# Nixie_Embedded_Supply.net
KiCad netlist of a schematic drawn in Altium Designer
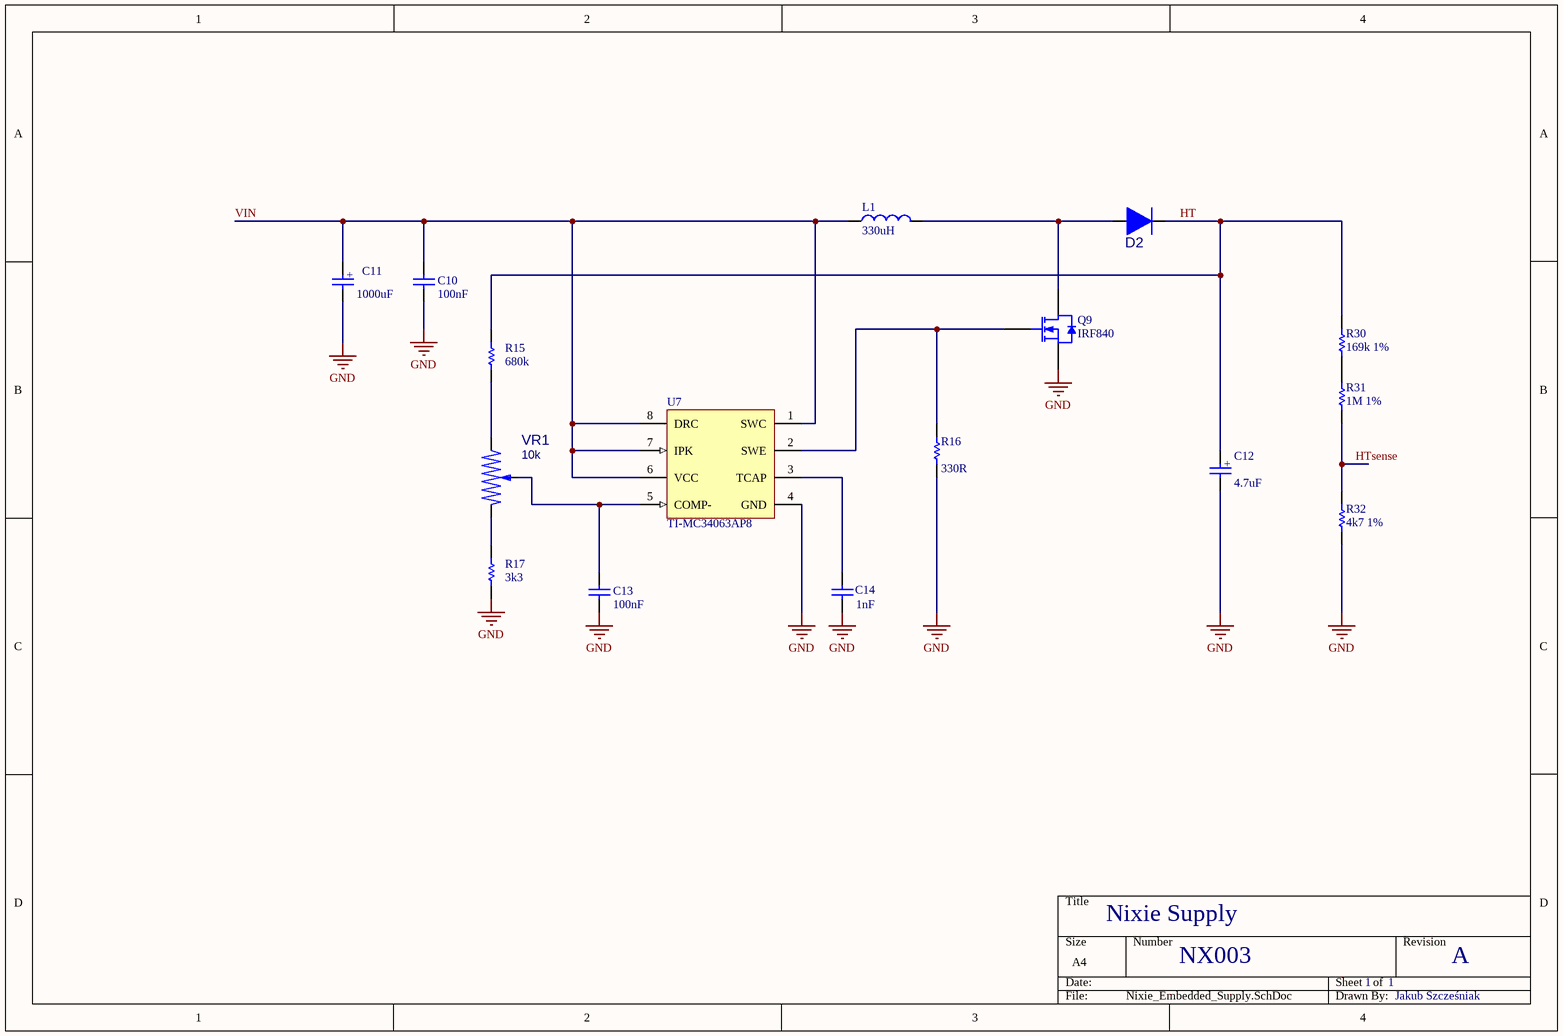
[diagram p0: Nixie_Embedded_Supply.SchDoc]

(export (version "E")
  (design (tool "Eeschema 10.0.6"))
  (components
    (comp (ref "C10")
      (value "100nF")
      (footprint "CAPC0805(2012)100_M")
      (description "CAP 100nF 16V ±5% 0805 (2012 Metric) Thickness 1mm SMD")
      (fields (field (name "TOLERANCE") "±5%") (field (name "Comment") "CAP 100nF 16V 0805(2012)"))
      (libsource (lib "Altium Content Vault") (part "CMP-1036-04400-1"))
    )
    (comp (ref "C11")
      (value "1000uF")
      (footprint "CAPsmd_rad10")
      (fields (field (name "Comment") "CAP_rad16x10"))
      (libsource (lib "Nixie_Supply") (part "CAP_rad16x10"))
    )
    (comp (ref "C12")
      (value "4.7uF")
      (footprint "CAP_HV")
      (fields (field (name "Comment") "CAP_HV"))
      (libsource (lib "Nixie_Supply") (part "CAP_HV"))
    )
    (comp (ref "C13")
      (value "100nF")
      (footprint "CAPC0805(2012)100_M")
      (description "CAP 100nF 16V ±5% 0805 (2012 Metric) Thickness 1mm SMD")
      (fields (field (name "TOLERANCE") "±5%") (field (name "Comment") "CAP 100nF 16V 0805(2012)"))
      (libsource (lib "Altium Content Vault") (part "CMP-1036-04400-1"))
    )
    (comp (ref "C14")
      (value "1nF")
      (footprint "CAPC0805(2012)100_M")
      (description "CAP 1nF 25V ±1% 0805 (2012 Metric) Thickness 1mm SMD")
      (fields (field (name "TOLERANCE") "±1%") (field (name "Comment") "CAP 1nF 25V 0805(2012)"))
      (libsource (lib "Altium Content Vault") (part "CMP-1036-02963-1"))
    )
    (comp (ref "D2")
      (value "BYV29-400")
      (footprint "D2PAK")
      (fields (field (name "PART NUMBER") "104-5508"))
      (libsource (lib "Nixie_Supply") (part "BYV29-400"))
    )
    (comp (ref "L1") (value "330uH") (footprint "Coil") (libsource (lib "Nixie_Supply") (part "L")))
    (comp (ref "Q9") (value "IRF840") (footprint "D2PAK") (libsource (lib "Nixie_Supply") (part "IRF840")))
    (comp (ref "R15")
      (value "680k")
      (footprint "RESC0805(2012)_M")
      (description "680K 0.125W 5% 0805 (2012 Metric)  SMD")
      (fields (field (name "POWER") "0.125 W") (field (name "TOLERANCE") "5 %"))
      (libsource (lib "Altium Content Vault") (part "CMP-1013-00142-1"))
    )
    (comp (ref "R16")
      (value "330R")
      (footprint "RESC0805(2012)_M")
      (description "330R 0.125W 5% 0805 (2012 Metric)  SMD")
      (fields (field (name "TOLERANCE") "5 %") (field (name "POWER") "0.125 W"))
      (libsource (lib "Altium Content Vault") (part "CMP-1013-00062-1"))
    )
    (comp (ref "R17")
      (value "3k3")
      (footprint "RESC0805(2012)_M")
      (description "3K3 0.125W 1% 0805 (2012 Metric)  SMD")
      (fields (field (name "TOLERANCE") "1 %") (field (name "POWER") "0.125 W"))
      (libsource (lib "Altium Content Vault") (part "CMP-1013-00567-1"))
    )
    (comp (ref "R30")
      (value "169k 1%")
      (footprint "RESC0805(2012)_M")
      (description "169K 0.125W 1% 0805 (2012 Metric)  SMD")
      (fields (field (name "POWER") "0.125 W") (field (name "TOLERANCE") "1 %"))
      (libsource (lib "Altium Content Vault") (part "CMP-1013-00760-1"))
    )
    (comp (ref "R31")
      (value "1M 1%")
      (footprint "RESC0805(2012)_M")
      (description "1M 0.125W 1% 0805 (2012 Metric)  SMD")
      (fields (field (name "POWER") "0.125 W") (field (name "TOLERANCE") "1 %"))
      (libsource (lib "Altium Content Vault") (part "CMP-1013-00849-1"))
    )
    (comp (ref "R32")
      (value "4k7 1%")
      (footprint "RESC0805(2012)_M")
      (description "4K7 0.125W 1% 0805 (2012 Metric)  SMD")
      (fields (field (name "POWER") "0.125 W") (field (name "TOLERANCE") "1 %"))
      (libsource (lib "Altium Content Vault") (part "RES"))
    )
    (comp (ref "U7")
      (value "TI-MC34063AP8")
      (footprint "SOIC8")
      (libsource (lib "Nixie_Supply") (part "TI-MC34063AP8"))
    )
    (comp (ref "VR1")
      (value "10k")
      (footprint "POT7x5")
      (description "Potentiometer")
      (fields (field (name "PART NUMBER") "119-1725"))
      (libsource (lib "Nixie_Supply") (part "RESPOT_ST-V01"))
    )
  )
  (nets
    (net (code "1") (name "/HT") (class "Default")
      (node (ref "C12") (pin "1") (pinfunction "1_1") (pintype "passive"))
      (node (ref "D2") (pin "2") (pinfunction "K_2") (pintype "passive"))
      (node (ref "R15") (pin "2") (pinfunction "2_2") (pintype "passive"))
      (node (ref "R30") (pin "2") (pinfunction "2_2") (pintype "passive"))
    )
    (net (code "2") (name "/HTsense") (class "Default")
      (node (ref "R31") (pin "1") (pinfunction "1_1") (pintype "passive"))
      (node (ref "R32") (pin "2") (pinfunction "2_2") (pintype "passive"))
    )
    (net (code "3") (name "/VIN") (class "Default")
      (node (ref "C10") (pin "2") (pinfunction "2_2") (pintype "passive"))
      (node (ref "C11") (pin "1") (pinfunction "1_1") (pintype "passive"))
      (node (ref "L1") (pin "1") (pinfunction "1_1") (pintype "passive"))
      (node (ref "U7") (pin "1") (pinfunction "SWC_1") (pintype "open_collector"))
      (node (ref "U7") (pin "6") (pinfunction "VCC_6") (pintype "power_in"))
      (node (ref "U7") (pin "7") (pinfunction "IPK_7") (pintype "input"))
      (node (ref "U7") (pin "8") (pinfunction "DRC_8") (pintype "open_collector"))
    )
    (net (code "4") (name "GND") (class "Default")
      (node (ref "C10") (pin "1") (pinfunction "1_1") (pintype "passive"))
      (node (ref "C11") (pin "2") (pinfunction "2_2") (pintype "passive"))
      (node (ref "C12") (pin "2") (pinfunction "2_2") (pintype "passive"))
      (node (ref "C13") (pin "1") (pinfunction "1_1") (pintype "passive"))
      (node (ref "C14") (pin "1") (pinfunction "1_1") (pintype "passive"))
      (node (ref "Q9") (pin "3") (pinfunction "S_3") (pintype "passive"))
      (node (ref "R16") (pin "1") (pinfunction "1_1") (pintype "passive"))
      (node (ref "R17") (pin "1") (pinfunction "1_1") (pintype "passive"))
      (node (ref "R32") (pin "1") (pinfunction "1_1") (pintype "passive"))
      (node (ref "U7") (pin "4") (pinfunction "GND_4") (pintype "power_in"))
    )
    (net (code "5") (name "Net-(D2-A)") (class "Default")
      (node (ref "D2") (pin "1") (pinfunction "A_1") (pintype "passive"))
      (node (ref "L1") (pin "2") (pinfunction "2_2") (pintype "passive"))
      (node (ref "Q9") (pin "2") (pinfunction "D_2") (pintype "passive"))
    )
    (net (code "6") (name "Net-(Q9-G)") (class "Default")
      (node (ref "Q9") (pin "1") (pinfunction "G_1") (pintype "passive"))
      (node (ref "R16") (pin "2") (pinfunction "2_2") (pintype "passive"))
      (node (ref "U7") (pin "2") (pinfunction "SWE_2") (pintype "open_emitter"))
    )
    (net (code "7") (name "Net-(R15-Pad1)") (class "Default")
      (node (ref "R15") (pin "1") (pinfunction "1_1") (pintype "passive"))
      (node (ref "VR1") (pin "3") (pinfunction "3_3") (pintype "passive"))
    )
    (net (code "8") (name "Net-(R17-Pad2)") (class "Default")
      (node (ref "R17") (pin "2") (pinfunction "2_2") (pintype "passive"))
      (node (ref "VR1") (pin "1") (pinfunction "1_1") (pintype "passive"))
    )
    (net (code "9") (name "Net-(R30-Pad1)") (class "Default")
      (node (ref "R30") (pin "1") (pinfunction "1_1") (pintype "passive"))
      (node (ref "R31") (pin "2") (pinfunction "2_2") (pintype "passive"))
    )
    (net (code "10") (name "Net-(U7-COMP-)") (class "Default")
      (node (ref "C13") (pin "2") (pinfunction "2_2") (pintype "passive"))
      (node (ref "U7") (pin "5") (pinfunction "COMP-_5") (pintype "input"))
      (node (ref "VR1") (pin "2") (pinfunction "2_2") (pintype "passive"))
    )
    (net (code "11") (name "Net-(U7-TCAP)") (class "Default")
      (node (ref "C14") (pin "2") (pinfunction "2_2") (pintype "passive"))
      (node (ref "U7") (pin "3") (pinfunction "TCAP_3") (pintype "passive"))
    )
  )
)
